# main.net
KiCad netlist of a schematic drawn in Altium Designer
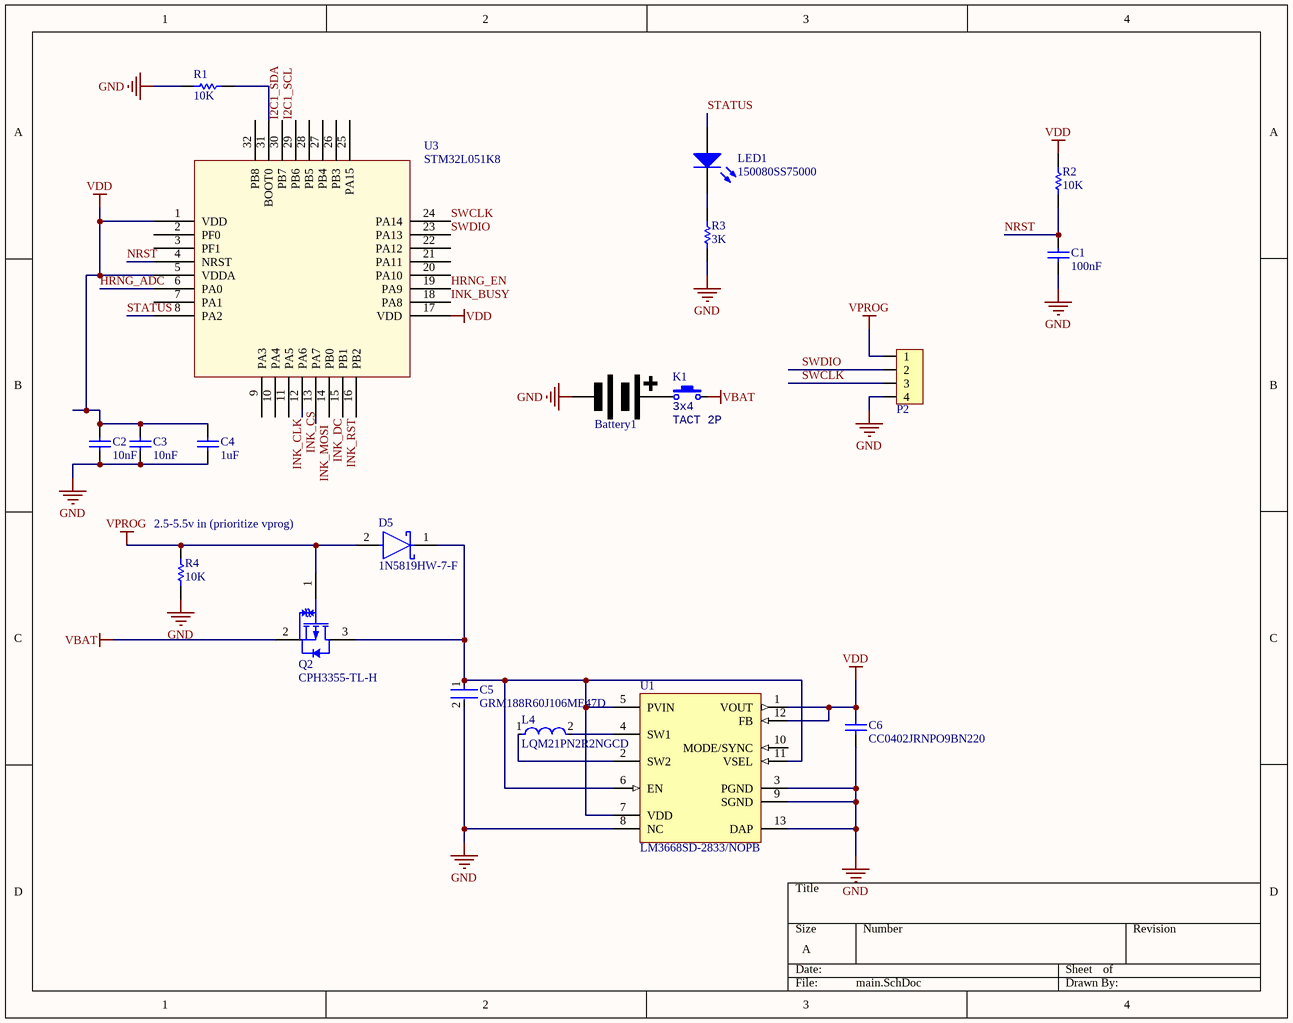
[diagram p0: main.SchDoc]

(export (version "E")
  (design (tool "Eeschema 10.0.6"))
  (components
    (comp (ref "Battery1")
      (value "Battery")
      (footprint "CR2032-1")
      (libsource (lib "L-ink") (part "Battery"))
    )
    (comp (ref "C1")
      (value "100nF")
      (footprint "C0402")
      (description "Capacitor, MLCC, 100nF, 16V, X7R, 10%, 0402, T=0,5mm")
      (fields
        (field (name "INTERNAL_PART_NUMBER") "MCD-00102")
        (field (name "MANUFACTURER_PART_NUMBER") "CC0402KRX7R7BB104")
        (field (name "PROVIDED_BY") "SUBCO")
      )
      (libsource (lib "MB1272") (part "MCD-00102"))
    )
    (comp (ref "C2")
      (value "10nF")
      (footprint "C0402")
      (description "Capacitor, MLCC, 10nF, 16V, X7R, 10%, 0402, T=0.5mm")
      (fields
        (field (name "INTERNAL_PART_NUMBER") "MCD-00011")
        (field (name "MANUFACTURER_PART_NUMBER") "CC0402KRX7R7BB103")
        (field (name "PROVIDED_BY") "SUBCO")
      )
      (libsource (lib "MB1272") (part "MCD-00011"))
    )
    (comp (ref "C3")
      (value "10nF")
      (footprint "C0402")
      (description "Capacitor, MLCC, 10nF, 16V, X7R, 10%, 0402, T=0.5mm")
      (fields
        (field (name "INTERNAL_PART_NUMBER") "MCD-00011")
        (field (name "MANUFACTURER_PART_NUMBER") "CC0402KRX7R7BB103")
        (field (name "PROVIDED_BY") "SUBCO")
      )
      (libsource (lib "MB1272") (part "MCD-00011"))
    )
    (comp (ref "C4")
      (value "1uF")
      (footprint "C0402")
      (description "Capacitor,1uF,6V3,X5R,10%,0402")
      (fields
        (field (name "INTERNAL_PART_NUMBER") "MCD-00095")
        (field (name "MANUFACTURER_PART_NUMBER") "GRM155R61E105KA12")
        (field (name "PROVIDED_BY") "SUBCO")
      )
      (libsource (lib "MB1272") (part "MCD-00095"))
    )
    (comp (ref "C5")
      (value "GRM188R60J106ME47D")
      (footprint "FP-GRM188-0_1-e0_2_0_55-IPC_A")
      (description "Chip Multilayer Ceramic Capacitors for General Purpose, 0603, 10uF, X5R, 15%, 20%, 6.3V")
      (fields (field (name "VOLTAGE") "6.3V") (field (name "TOLERANCE") "20%"))
      (libsource (lib "Altium Content Vault") (part "02cd4be3c70576c341d710602a673aa"))
    )
    (comp (ref "C6")
      (value "CC0402JRNPO9BN220")
      (footprint "CAPC1005X55X25ML05T05")
      (description "Chip Capacitor, 22 pF, +/- 5%, 50 V, -55 to 125 degC, 0402 (1005 Metric), RoHS, Tape and Reel")
      (fields (field (name "MANUFACTURER") "Yageo") (field (name "TOLERANCE") "5%"))
      (libsource (lib "Altium Content Vault") (part "CAP-NP-2"))
    )
    (comp (ref "D5")
      (value "1N5819HW-7-F")
      (footprint "FP-SOD123-IPC_A")
      (description "DIODE SCHOTTKY 40V 1A SOD123")
      (libsource (lib "Altium Content Vault") (part "1d6ec82d83fb6aee721767c19dac4b9"))
    )
    (comp (ref "K1")
      (value "3x4")
      (footprint "ButtonTACT_3x4x2_180H")
      (description "Button")
      (fields (field (name "TYPE") "TACT 2P") (field (name "Comment") "TACT 2P"))
      (libsource (lib "L-ink") (part "ButtonTACT_3x4x2_180"))
    )
    (comp (ref "L4")
      (value "LQM21PN2R2NGCD")
      (footprint "FP-LQM21PH_G0-IPC_C")
      (description "Multilayer Type Inductor for Power Lines, 0805 (2012), 2.2μH, 30%, 0.288Ω, 0.8A")
      (fields (field (name "TOLERANCE") "30%"))
      (libsource (lib "Altium Content Vault") (part "725321dda6339637d4d059423bc1c3c"))
    )
    (comp (ref "LED1")
      (value "150080SS75000")
      (footprint "0805_A")
      (description "SMD mono-color Chip LED, WL-SMCW, Super Red")
      (fields (field (name "MANUFACTURER") "Wuerth Elektronik"))
      (libsource (lib "Altium Content Vault") (part "WE-LED_K1A2-2"))
    )
    (comp (ref "P2") (value "HDR1x4_2.0") (footprint "HDR 4_2") (libsource (lib "L-ink") (part "HDR1x4_2.0")))
    (comp (ref "Q2")
      (value "CPH3355-TL-H")
      (footprint "ONSC-CPH-3_V")
      (description "P-Channel Power MOSFET, -30 V, -2.5 A, 156 mOhm, 3-Pin CPH, Pb-Free, Tape and Reel")
      (fields (field (name "MANUFACTURER") "On Semiconductor"))
      (libsource (lib "Altium Content Vault") (part "ONSC-PMOS-G1S2D3-3"))
    )
    (comp (ref "R1")
      (value "10K")
      (footprint "R0402")
      (description "Resistor,10K,0402,1%,1/16W")
      (fields
        (field (name "INTERNAL_PART_NUMBER") "MCD-00053")
        (field (name "MANUFACTURER_PART_NUMBER") "RC0402FR-0710KL")
        (field (name "PROVIDED_BY") "SUBCO")
      )
      (libsource (lib "MB1272") (part "MCD-00053"))
    )
    (comp (ref "R2")
      (value "10K")
      (footprint "R0402")
      (description "Resistor,10K,0402,1%,1/16W")
      (fields
        (field (name "INTERNAL_PART_NUMBER") "MCD-00053")
        (field (name "MANUFACTURER_PART_NUMBER") "RC0402FR-0710KL")
        (field (name "PROVIDED_BY") "SUBCO")
      )
      (libsource (lib "MB1272") (part "MCD-00053"))
    )
    (comp (ref "R3")
      (value "3K")
      (footprint "R0402")
      (description "Resistor,3K,0402,1%,1/16W")
      (fields
        (field (name "INTERNAL_PART_NUMBER") "MCD-00185")
        (field (name "MANUFACTURER_PART_NUMBER") "RC0402FR-073KL")
        (field (name "PROVIDED_BY") "SUBCO")
      )
      (libsource (lib "MB1272") (part "MCD-00185"))
    )
    (comp (ref "R4")
      (value "10K")
      (footprint "R0402")
      (description "Resistor,10K,0402,1%,1/16W")
      (fields
        (field (name "INTERNAL_PART_NUMBER") "MCD-00053")
        (field (name "MANUFACTURER_PART_NUMBER") "RC0402FR-0710KL")
        (field (name "PROVIDED_BY") "SUBCO")
      )
      (libsource (lib "MB1272") (part "MCD-00053"))
    )
    (comp (ref "U1")
      (value "LM3668SD-2833/NOPB")
      (footprint "DQB0012A_V")
      (description "1A, High Efficiency Dual Mode Single Inductor Buck-Boost DC/DC Converter, 12-pin LLP, Pb-Free")
      (fields (field (name "MANUFACTURER") "Texas Instruments"))
      (libsource (lib "Altium Content Vault") (part "PM-DCDC-LM3668-13"))
    )
    (comp (ref "U3")
      (value "STM32L051K8")
      (footprint "QFN-32")
      (libsource (lib "L-ink") (part "STM32L051K8"))
    )
  )
  (nets
    (net (code "1") (name "/HRNG_ADC") (class "Default")
      (node (ref "U3") (pin "6") (pinfunction "PA0_6") (pintype "passive"))
    )
    (net (code "2") (name "/HRNG_EN") (class "Default")
      (node (ref "U3") (pin "19") (pinfunction "PA9_19") (pintype "passive"))
    )
    (net (code "3") (name "/I2C1_SCL") (class "Default")
      (node (ref "U3") (pin "29") (pinfunction "PB6_29") (pintype "passive"))
    )
    (net (code "4") (name "/I2C1_SDA") (class "Default")
      (node (ref "U3") (pin "30") (pinfunction "PB7_30") (pintype "passive"))
    )
    (net (code "5") (name "/INK_BUSY") (class "Default")
      (node (ref "U3") (pin "18") (pinfunction "PA8_18") (pintype "passive"))
    )
    (net (code "6") (name "/INK_CLK") (class "Default")
      (node (ref "U3") (pin "11") (pinfunction "PA5_11") (pintype "passive"))
    )
    (net (code "7") (name "/INK_CS") (class "Default")
      (node (ref "U3") (pin "12") (pinfunction "PA6_12") (pintype "passive"))
    )
    (net (code "8") (name "/INK_DC") (class "Default")
      (node (ref "U3") (pin "14") (pinfunction "PB0_14") (pintype "passive"))
    )
    (net (code "9") (name "/INK_MOSI") (class "Default")
      (node (ref "U3") (pin "13") (pinfunction "PA7_13") (pintype "passive"))
    )
    (net (code "10") (name "/INK_RST") (class "Default")
      (node (ref "U3") (pin "15") (pinfunction "PB1_15") (pintype "passive"))
    )
    (net (code "11") (name "/NRST") (class "Default")
      (node (ref "C1") (pin "2") (pinfunction "2_2") (pintype "passive"))
      (node (ref "R2") (pin "1") (pinfunction "1_1") (pintype "passive"))
      (node (ref "U3") (pin "4") (pinfunction "NRST_4") (pintype "passive"))
    )
    (net (code "12") (name "/STATUS") (class "Default")
      (node (ref "LED1") (pin "2") (pinfunction "A_2") (pintype "passive"))
      (node (ref "U3") (pin "8") (pinfunction "PA2_8") (pintype "passive"))
    )
    (net (code "13") (name "/SWCLK") (class "Default")
      (node (ref "P2") (pin "3") (pinfunction "3_3") (pintype "passive"))
      (node (ref "U3") (pin "24") (pinfunction "PA14_24") (pintype "passive"))
    )
    (net (code "14") (name "/SWDIO") (class "Default")
      (node (ref "P2") (pin "2") (pinfunction "2_2") (pintype "passive"))
      (node (ref "U3") (pin "23") (pinfunction "PA13_23") (pintype "passive"))
    )
    (net (code "15") (name "GND") (class "Default")
      (node (ref "Battery1") (pin "1") (pinfunction "-_1") (pintype "passive"))
      (node (ref "C1") (pin "1") (pinfunction "1_1") (pintype "passive"))
      (node (ref "C2") (pin "1") (pinfunction "1_1") (pintype "passive"))
      (node (ref "C3") (pin "1") (pinfunction "1_1") (pintype "passive"))
      (node (ref "C4") (pin "1") (pinfunction "1_1") (pintype "passive"))
      (node (ref "C5") (pin "2") (pinfunction "2_2") (pintype "passive"))
      (node (ref "C6") (pin "1") (pinfunction "1_1") (pintype "passive"))
      (node (ref "P2") (pin "4") (pinfunction "4_4") (pintype "passive"))
      (node (ref "R1") (pin "2") (pinfunction "2_2") (pintype "passive"))
      (node (ref "R3") (pin "1") (pinfunction "1_1") (pintype "passive"))
      (node (ref "R4") (pin "1") (pinfunction "1_1") (pintype "passive"))
      (node (ref "U1") (pin "13") (pinfunction "DAP_13") (pintype "power_in"))
      (node (ref "U1") (pin "3") (pinfunction "PGND_3") (pintype "power_in"))
      (node (ref "U1") (pin "8") (pinfunction "NC_8") (pintype "passive"))
      (node (ref "U1") (pin "9") (pinfunction "SGND_9") (pintype "power_in"))
    )
    (net (code "16") (name "Net-(Battery1-+)") (class "Default")
      (node (ref "Battery1") (pin "2") (pinfunction "+_2") (pintype "passive"))
      (node (ref "K1") (pin "1") (pinfunction "1_1") (pintype "passive"))
    )
    (net (code "17") (name "Net-(D5-C)") (class "Default")
      (node (ref "C5") (pin "1") (pinfunction "1_1") (pintype "passive"))
      (node (ref "D5") (pin "1") (pinfunction "C_1") (pintype "passive"))
      (node (ref "Q2") (pin "3") (pinfunction "D_3") (pintype "passive"))
      (node (ref "U1") (pin "11") (pinfunction "VSEL_11") (pintype "input"))
      (node (ref "U1") (pin "5") (pinfunction "PVIN_5") (pintype "power_in"))
      (node (ref "U1") (pin "6") (pinfunction "EN_6") (pintype "input"))
      (node (ref "U1") (pin "7") (pinfunction "VDD_7") (pintype "power_in"))
    )
    (net (code "18") (name "Net-(LED1-K)") (class "Default")
      (node (ref "LED1") (pin "1") (pinfunction "K_1") (pintype "passive"))
      (node (ref "R3") (pin "2") (pinfunction "2_2") (pintype "passive"))
    )
    (net (code "19") (name "Net-(U1-SW1)") (class "Default")
      (node (ref "L4") (pin "2") (pinfunction "2_2") (pintype "passive"))
      (node (ref "U1") (pin "4") (pinfunction "SW1_4") (pintype "power_in"))
    )
    (net (code "20") (name "Net-(U1-SW2)") (class "Default")
      (node (ref "L4") (pin "1") (pinfunction "1_1") (pintype "passive"))
      (node (ref "U1") (pin "2") (pinfunction "SW2_2") (pintype "power_in"))
    )
    (net (code "21") (name "Net-(U3-BOOT0)") (class "Default")
      (node (ref "R1") (pin "1") (pinfunction "1_1") (pintype "passive"))
      (node (ref "U3") (pin "31") (pinfunction "BOOT0_31") (pintype "passive"))
    )
    (net (code "22") (name "VBAT") (class "Default")
      (node (ref "K1") (pin "2") (pinfunction "2_2") (pintype "passive"))
      (node (ref "Q2") (pin "2") (pinfunction "S_2") (pintype "passive"))
    )
    (net (code "23") (name "VDD") (class "Default")
      (node (ref "C2") (pin "2") (pinfunction "2_2") (pintype "passive"))
      (node (ref "C3") (pin "2") (pinfunction "2_2") (pintype "passive"))
      (node (ref "C4") (pin "2") (pinfunction "2_2") (pintype "passive"))
      (node (ref "C6") (pin "2") (pinfunction "2_2") (pintype "passive"))
      (node (ref "R2") (pin "2") (pinfunction "2_2") (pintype "passive"))
      (node (ref "U1") (pin "1") (pinfunction "VOUT_1") (pintype "output"))
      (node (ref "U1") (pin "12") (pinfunction "FB_12") (pintype "input"))
      (node (ref "U3") (pin "1") (pinfunction "VDD_1") (pintype "passive"))
      (node (ref "U3") (pin "17") (pinfunction "VDD_17") (pintype "passive"))
      (node (ref "U3") (pin "5") (pinfunction "VDDA_5") (pintype "passive"))
    )
    (net (code "24") (name "VPROG") (class "Default")
      (node (ref "D5") (pin "2") (pinfunction "A_2") (pintype "passive"))
      (node (ref "P2") (pin "1") (pinfunction "1_1") (pintype "passive"))
      (node (ref "Q2") (pin "1") (pinfunction "G_1") (pintype "passive"))
      (node (ref "R4") (pin "2") (pinfunction "2_2") (pintype "passive"))
    )
    (net (code "25") (name "unconnected-(U1-MODE{slash}SYNC-Pad10)") (class "Default")
      (node (ref "U1") (pin "10") (pinfunction "MODE/SYNC_10") (pintype "input"))
    )
    (net (code "26") (name "unconnected-(U3-PA1-Pad7)") (class "Default")
      (node (ref "U3") (pin "7") (pinfunction "PA1_7") (pintype "passive"))
    )
    (net (code "27") (name "unconnected-(U3-PA3-Pad9)") (class "Default")
      (node (ref "U3") (pin "9") (pinfunction "PA3_9") (pintype "passive"))
    )
    (net (code "28") (name "unconnected-(U3-PA4-Pad10)") (class "Default")
      (node (ref "U3") (pin "10") (pinfunction "PA4_10") (pintype "passive"))
    )
    (net (code "29") (name "unconnected-(U3-PA10-Pad20)") (class "Default")
      (node (ref "U3") (pin "20") (pinfunction "PA10_20") (pintype "passive"))
    )
    (net (code "30") (name "unconnected-(U3-PA11-Pad21)") (class "Default")
      (node (ref "U3") (pin "21") (pinfunction "PA11_21") (pintype "passive"))
    )
    (net (code "31") (name "unconnected-(U3-PA12-Pad22)") (class "Default")
      (node (ref "U3") (pin "22") (pinfunction "PA12_22") (pintype "passive"))
    )
    (net (code "32") (name "unconnected-(U3-PA15-Pad25)") (class "Default")
      (node (ref "U3") (pin "25") (pinfunction "PA15_25") (pintype "passive"))
    )
    (net (code "33") (name "unconnected-(U3-PB2-Pad16)") (class "Default")
      (node (ref "U3") (pin "16") (pinfunction "PB2_16") (pintype "passive"))
    )
    (net (code "34") (name "unconnected-(U3-PB3-Pad26)") (class "Default")
      (node (ref "U3") (pin "26") (pinfunction "PB3_26") (pintype "passive"))
    )
    (net (code "35") (name "unconnected-(U3-PB4-Pad27)") (class "Default")
      (node (ref "U3") (pin "27") (pinfunction "PB4_27") (pintype "passive"))
    )
    (net (code "36") (name "unconnected-(U3-PB5-Pad28)") (class "Default")
      (node (ref "U3") (pin "28") (pinfunction "PB5_28") (pintype "passive"))
    )
    (net (code "37") (name "unconnected-(U3-PB8-Pad32)") (class "Default")
      (node (ref "U3") (pin "32") (pinfunction "PB8_32") (pintype "passive"))
    )
    (net (code "38") (name "unconnected-(U3-PF0-Pad2)") (class "Default")
      (node (ref "U3") (pin "2") (pinfunction "PF0_2") (pintype "passive"))
    )
    (net (code "39") (name "unconnected-(U3-PF1-Pad3)") (class "Default")
      (node (ref "U3") (pin "3") (pinfunction "PF1_3") (pintype "passive"))
    )
  )
)
